# isolation.net
KiCad netlist of a schematic drawn in EAGLE
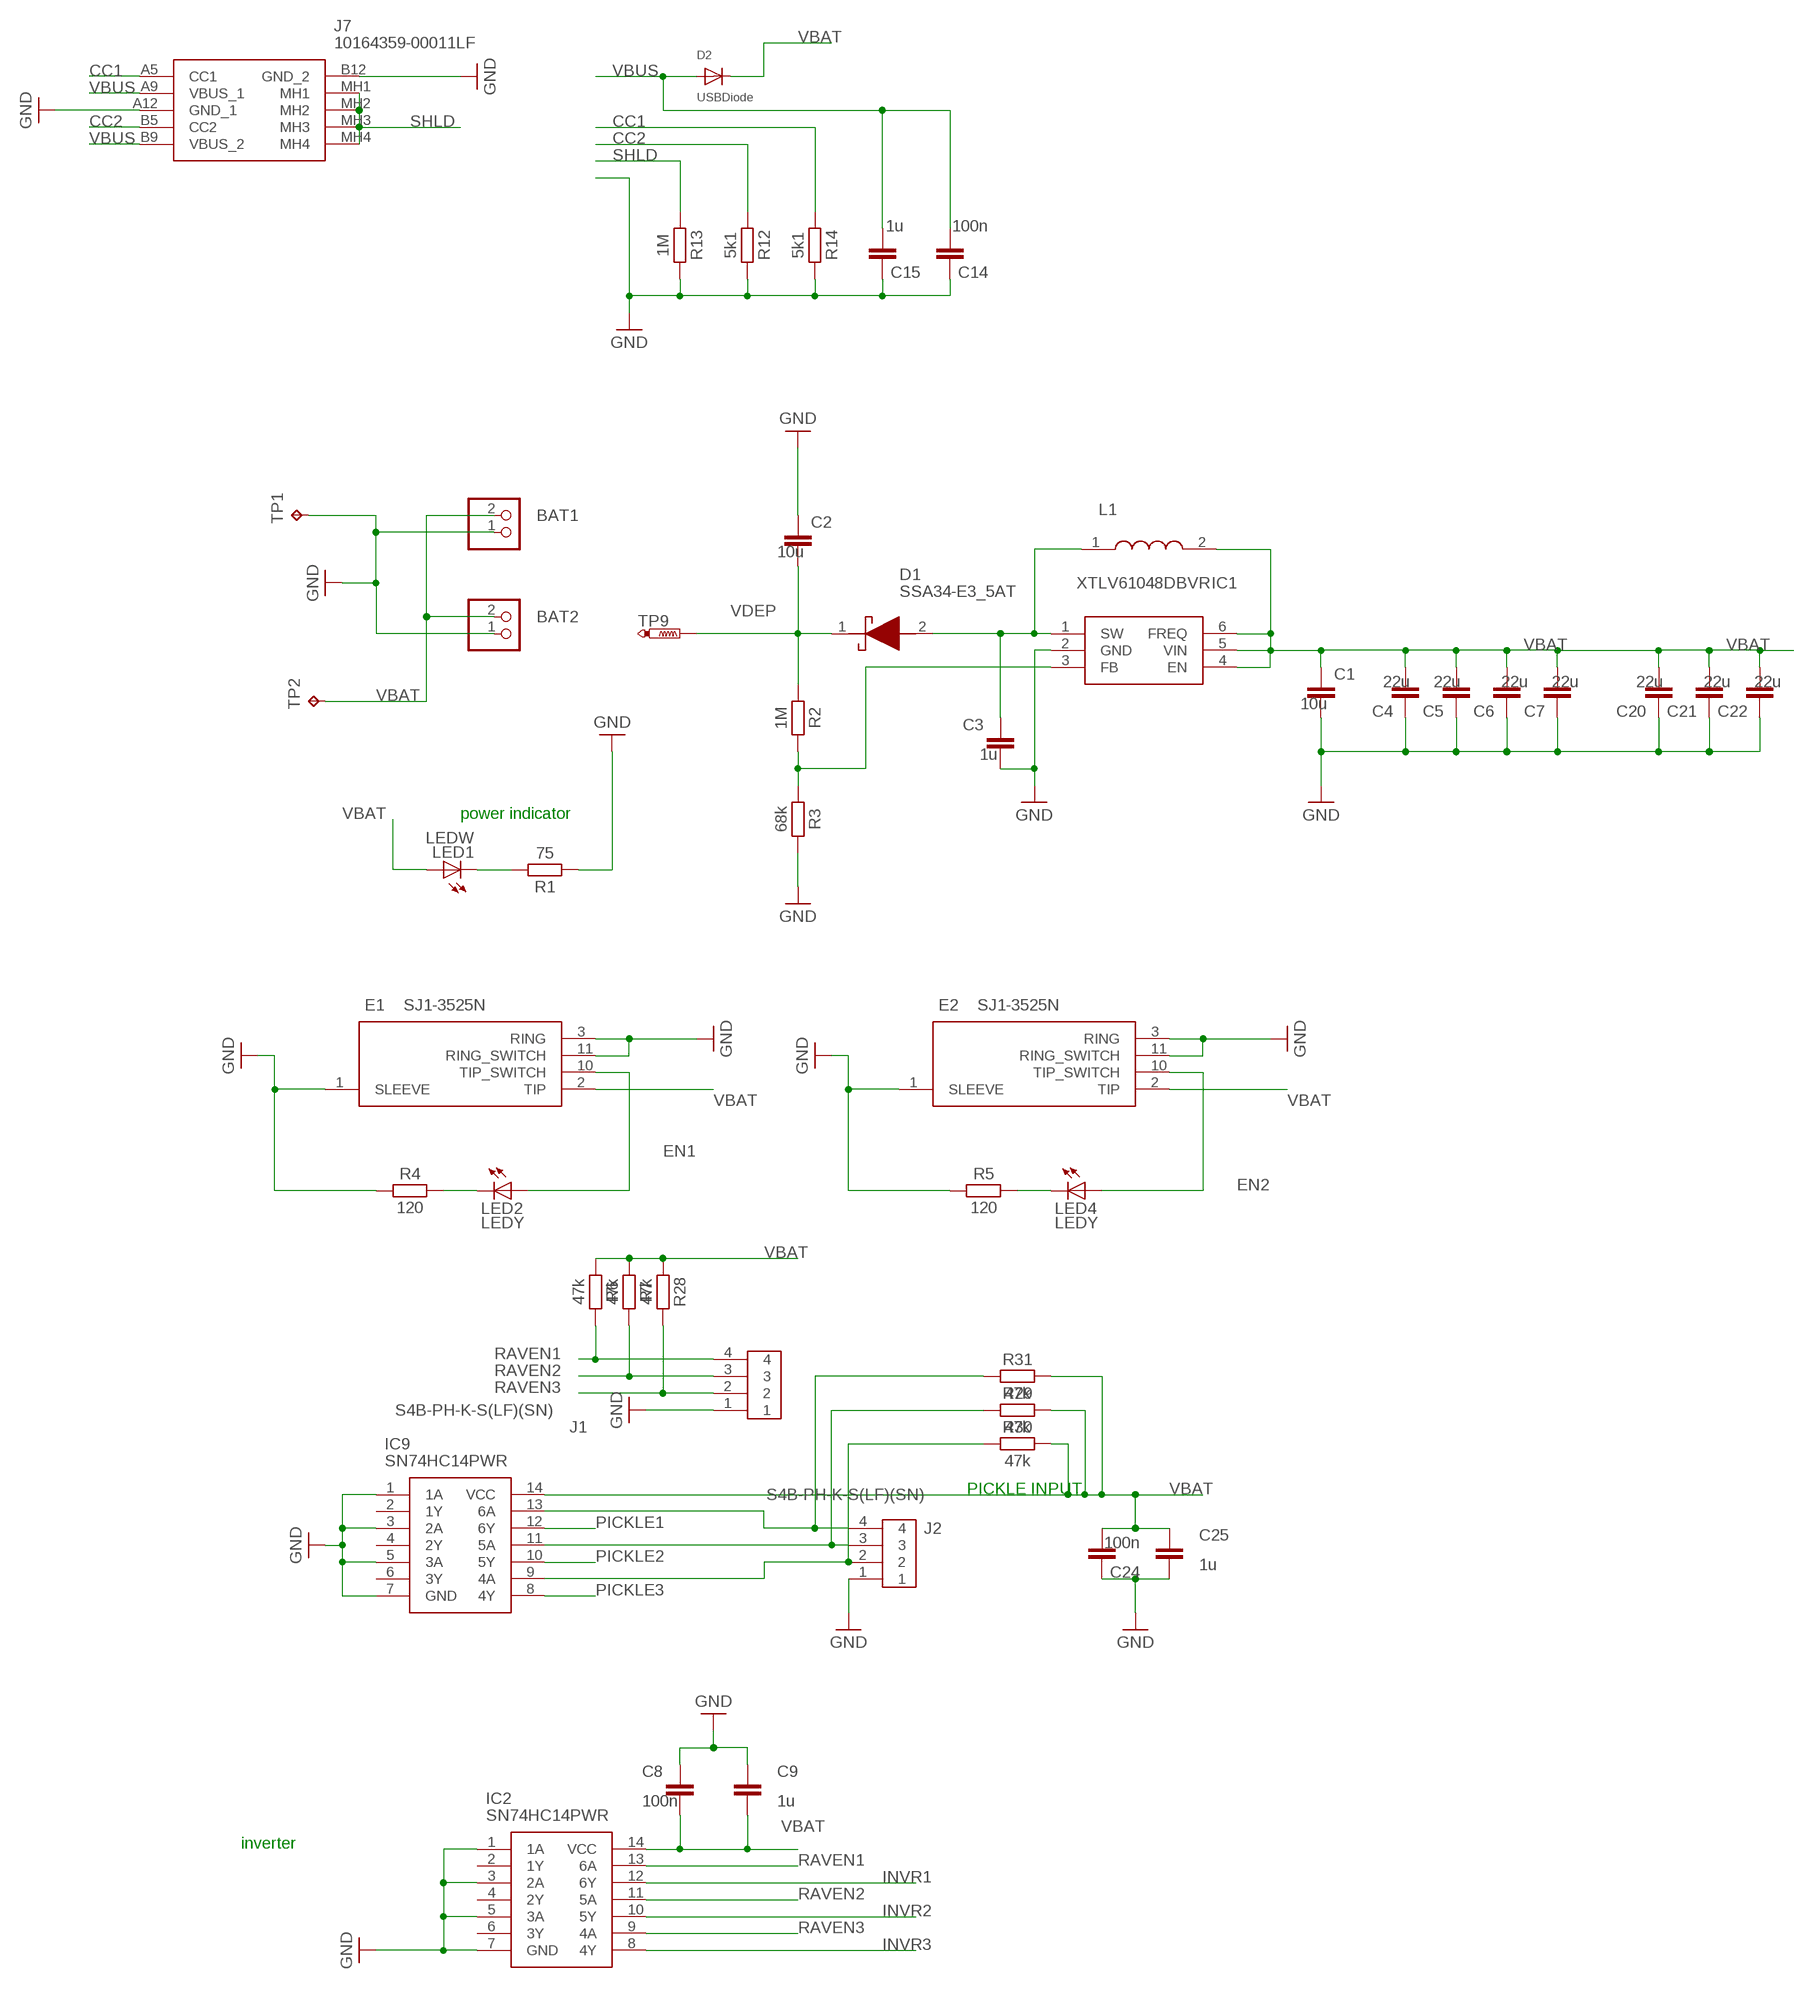
[diagram p0: schematic, sheet 1, part 1 of 2]
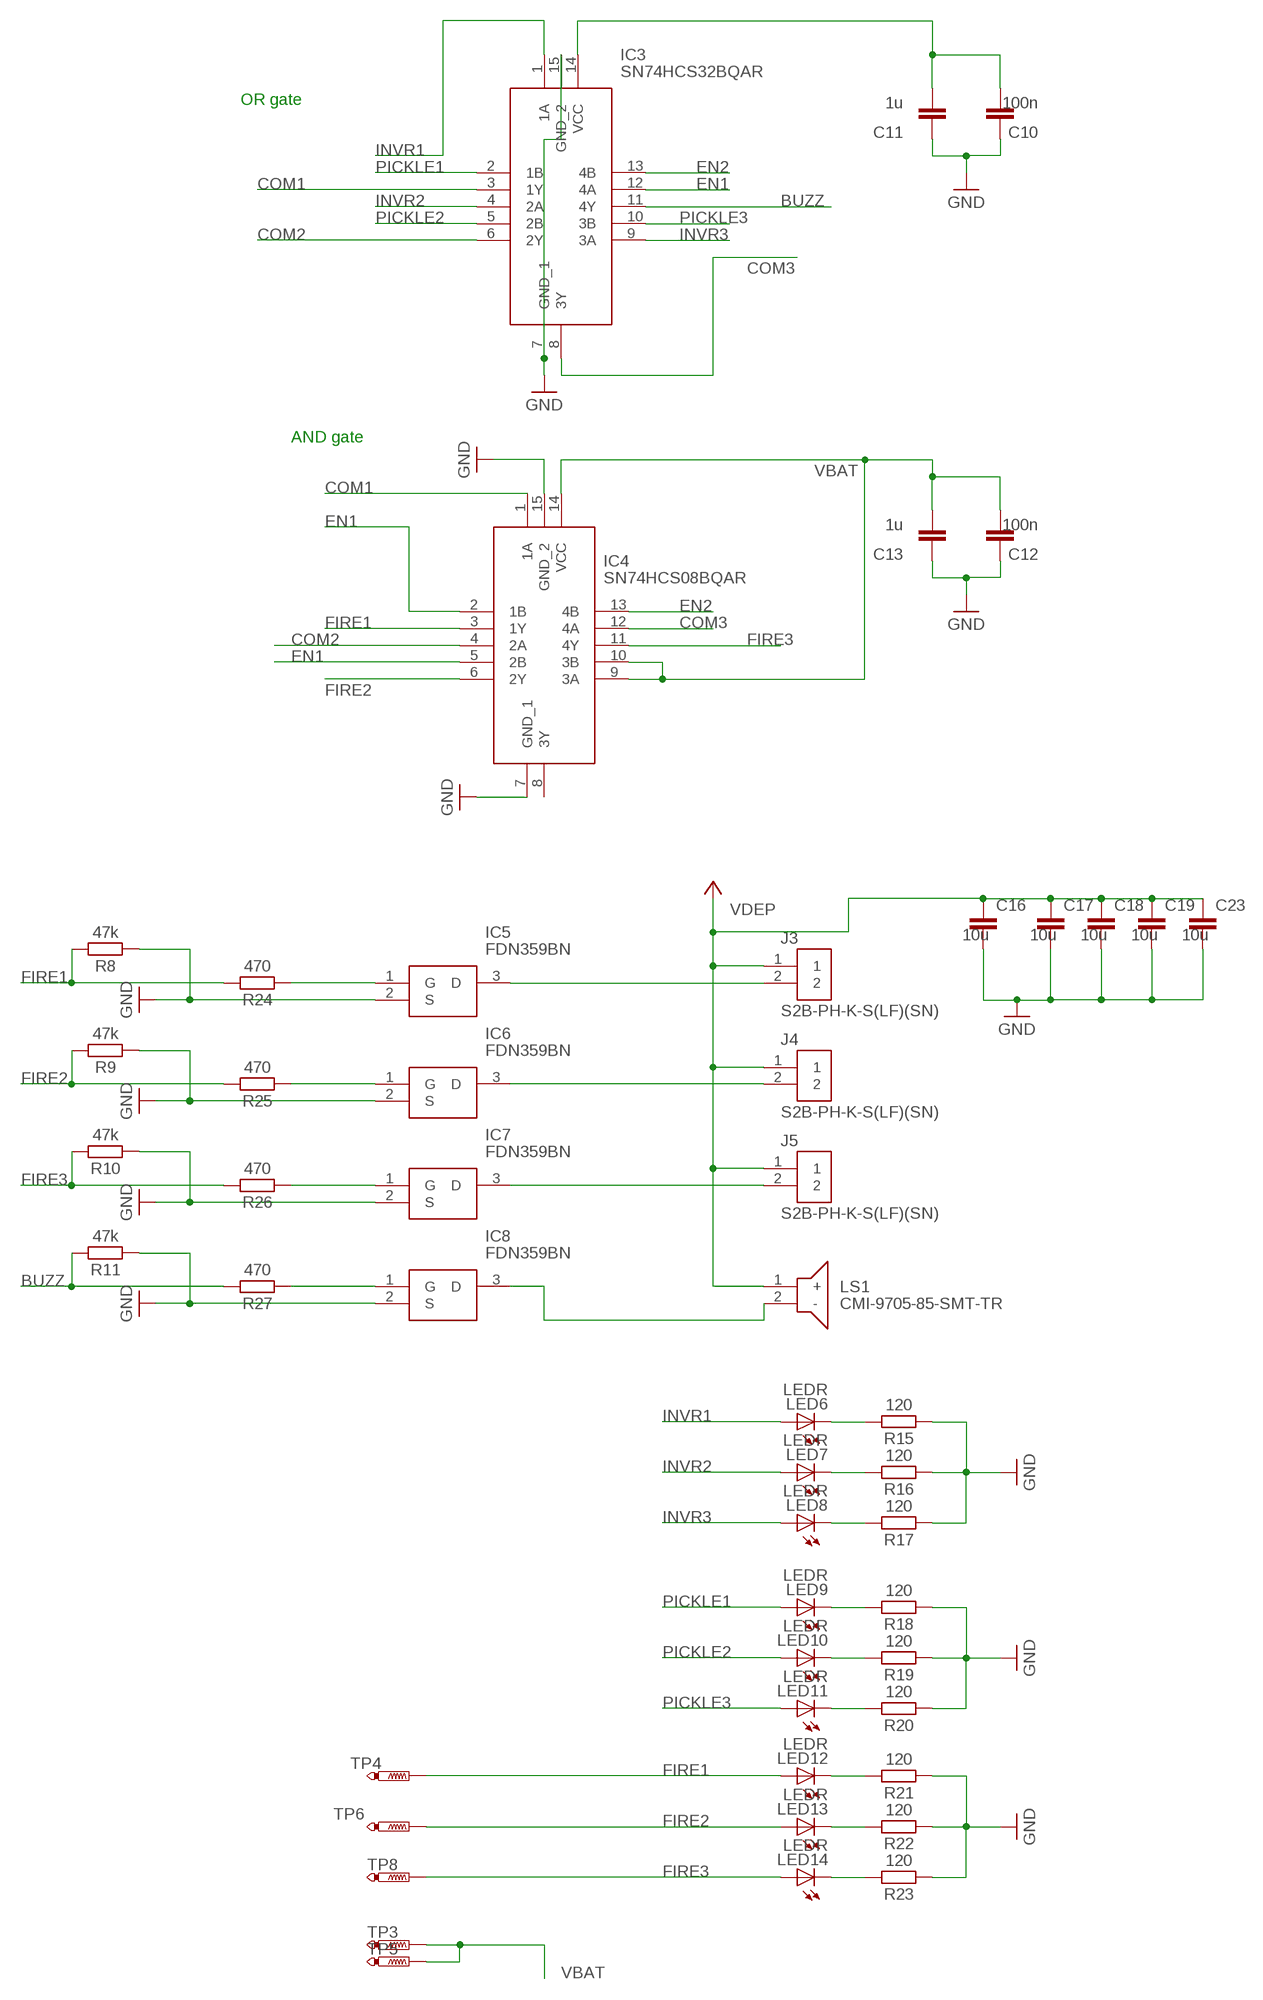
[diagram p1: schematic, sheet 1, part 2 of 2]

(export (version "E")
  (design (tool "Eeschema 10.0.6"))
  (components
    (comp (ref "BAT1")
      (value "JST_2PIN-THM-RA")
      (footprint "eagle-import:JST-PH-2-THM-RA")
      (libsource (lib "eagle-import") (part "JST_2PIN-THM-RA"))
    )
    (comp (ref "BAT2")
      (value "JST_2PIN-THM-RA")
      (footprint "eagle-import:JST-PH-2-THM-RA")
      (libsource (lib "eagle-import") (part "JST_2PIN-THM-RA"))
    )
    (comp (ref "C1")
      (value "10u")
      (footprint "eagle-import:CAPC1005X60")
      (libsource (lib "eagle-import") (part "CCHIP-0402(1005-METRIC)_"))
    )
    (comp (ref "C2")
      (value "10u")
      (footprint "eagle-import:CAPC1608X85")
      (libsource (lib "eagle-import") (part "CCHIP-0603(1608-METRIC)_"))
    )
    (comp (ref "C3")
      (value "1u")
      (footprint "eagle-import:CAPC1005X60")
      (libsource (lib "eagle-import") (part "CCHIP-0402(1005-METRIC)_"))
    )
    (comp (ref "C4")
      (value "22u")
      (footprint "eagle-import:CAPC1608X85")
      (libsource (lib "eagle-import") (part "CCHIP-0603(1608-METRIC)_"))
    )
    (comp (ref "C5")
      (value "22u")
      (footprint "eagle-import:CAPC1608X85")
      (libsource (lib "eagle-import") (part "CCHIP-0603(1608-METRIC)_"))
    )
    (comp (ref "C6")
      (value "22u")
      (footprint "eagle-import:CAPC1608X85")
      (libsource (lib "eagle-import") (part "CCHIP-0603(1608-METRIC)_"))
    )
    (comp (ref "C7")
      (value "22u")
      (footprint "eagle-import:CAPC1608X85")
      (libsource (lib "eagle-import") (part "CCHIP-0603(1608-METRIC)_"))
    )
    (comp (ref "C8")
      (value "100n")
      (footprint "eagle-import:CAPC1005X60")
      (libsource (lib "eagle-import") (part "CCHIP-0402(1005-METRIC)_"))
    )
    (comp (ref "C9")
      (value "1u")
      (footprint "eagle-import:CAPC1005X60")
      (libsource (lib "eagle-import") (part "CCHIP-0402(1005-METRIC)_"))
    )
    (comp (ref "C10")
      (value "100n")
      (footprint "eagle-import:CAPC1005X60")
      (libsource (lib "eagle-import") (part "CCHIP-0402(1005-METRIC)_"))
    )
    (comp (ref "C11")
      (value "1u")
      (footprint "eagle-import:CAPC1005X60")
      (libsource (lib "eagle-import") (part "CCHIP-0402(1005-METRIC)_"))
    )
    (comp (ref "C12")
      (value "100n")
      (footprint "eagle-import:CAPC1005X60")
      (libsource (lib "eagle-import") (part "CCHIP-0402(1005-METRIC)_"))
    )
    (comp (ref "C13")
      (value "1u")
      (footprint "eagle-import:CAPC1005X60")
      (libsource (lib "eagle-import") (part "CCHIP-0402(1005-METRIC)_"))
    )
    (comp (ref "C14")
      (value "100n")
      (footprint "eagle-import:CAPC1005X60")
      (libsource (lib "eagle-import") (part "CCHIP-0402(1005-METRIC)_"))
    )
    (comp (ref "C15")
      (value "1u")
      (footprint "eagle-import:CAPC1005X60")
      (libsource (lib "eagle-import") (part "CCHIP-0402(1005-METRIC)_"))
    )
    (comp (ref "C16")
      (value "10u")
      (footprint "eagle-import:CAPC1608X85")
      (libsource (lib "eagle-import") (part "CCHIP-0603(1608-METRIC)_"))
    )
    (comp (ref "C17")
      (value "10u")
      (footprint "eagle-import:CAPC1608X85")
      (libsource (lib "eagle-import") (part "CCHIP-0603(1608-METRIC)_"))
    )
    (comp (ref "C18")
      (value "10u")
      (footprint "eagle-import:CAPC1608X85")
      (libsource (lib "eagle-import") (part "CCHIP-0603(1608-METRIC)_"))
    )
    (comp (ref "C19")
      (value "10u")
      (footprint "eagle-import:CAPC1608X85")
      (libsource (lib "eagle-import") (part "CCHIP-0603(1608-METRIC)_"))
    )
    (comp (ref "C20")
      (value "22u")
      (footprint "eagle-import:CAPC1608X85")
      (libsource (lib "eagle-import") (part "CCHIP-0603(1608-METRIC)_"))
    )
    (comp (ref "C21")
      (value "22u")
      (footprint "eagle-import:CAPC1608X85")
      (libsource (lib "eagle-import") (part "CCHIP-0603(1608-METRIC)_"))
    )
    (comp (ref "C22")
      (value "22u")
      (footprint "eagle-import:CAPC1608X85")
      (libsource (lib "eagle-import") (part "CCHIP-0603(1608-METRIC)_"))
    )
    (comp (ref "C23")
      (value "10u")
      (footprint "eagle-import:CAPC1608X85")
      (libsource (lib "eagle-import") (part "CCHIP-0603(1608-METRIC)_"))
    )
    (comp (ref "C24")
      (value "100n")
      (footprint "eagle-import:CAPC1005X60")
      (libsource (lib "eagle-import") (part "CCHIP-0402(1005-METRIC)_"))
    )
    (comp (ref "C25")
      (value "1u")
      (footprint "eagle-import:CAPC1005X60")
      (libsource (lib "eagle-import") (part "CCHIP-0402(1005-METRIC)_"))
    )
    (comp (ref "D1")
      (value "SSA34-E3_5AT")
      (footprint "eagle-import:DIOM5127X229N")
      (fields
        (field (name "ARROW_PART_NUMBER") "SSA34-E3/5AT")
        (field (name "MOUSER_PART_NUMBER") "625-SSA34-E3/5AT")
      )
      (libsource (lib "eagle-import") (part "SSA34-E3_5AT"))
    )
    (comp (ref "D2")
      (value "USBDiode")
      (footprint "eagle-import:SOD-123FL")
      (libsource (lib "eagle-import") (part "DIODE_SOD-123FL"))
    )
    (comp (ref "E1")
      (value "SJ1-3525N")
      (footprint "eagle-import:SJ13525N")
      (libsource (lib "eagle-import") (part "SJ1-3525N"))
    )
    (comp (ref "E2")
      (value "SJ1-3525N")
      (footprint "eagle-import:SJ13525N")
      (libsource (lib "eagle-import") (part "SJ1-3525N"))
    )
    (comp (ref "IC1")
      (value "XTLV61048DBVR")
      (footprint "eagle-import:SOT95P280X145-6N")
      (libsource (lib "eagle-import") (part "XTLV61048DBVR"))
    )
    (comp (ref "IC2")
      (value "SN74HC14PWR")
      (footprint "eagle-import:SOP65P640X120-14N")
      (fields (field (name "MOUSER_PART_NUMBER") "595-SN74HC14PWR"))
      (libsource (lib "eagle-import") (part "SN74HC14PWR"))
    )
    (comp (ref "IC3")
      (value "SN74HCS32BQAR")
      (footprint "eagle-import:SN74HCS32BQAR")
      (fields (field (name "MOUSER_PART_NUMBER") "595-SN74HCS32BQAR"))
      (libsource (lib "eagle-import") (part "SN74HCS32BQAR"))
    )
    (comp (ref "IC4")
      (value "SN74HCS08BQAR")
      (footprint "eagle-import:SN74HCS08BQAR")
      (fields (field (name "MOUSER_PART_NUMBER") "595-SN74HCS08BQAR"))
      (libsource (lib "eagle-import") (part "SN74HCS08BQAR"))
    )
    (comp (ref "IC5")
      (value "FDN359BN")
      (footprint "eagle-import:SOT95P251X112-3N")
      (fields (field (name "MOUSER_PART_NUMBER") "512-FDN359BN"))
      (libsource (lib "eagle-import") (part "FDN359BN"))
    )
    (comp (ref "IC6")
      (value "FDN359BN")
      (footprint "eagle-import:SOT95P251X112-3N")
      (fields (field (name "MOUSER_PART_NUMBER") "512-FDN359BN"))
      (libsource (lib "eagle-import") (part "FDN359BN"))
    )
    (comp (ref "IC7")
      (value "FDN359BN")
      (footprint "eagle-import:SOT95P251X112-3N")
      (fields (field (name "MOUSER_PART_NUMBER") "512-FDN359BN"))
      (libsource (lib "eagle-import") (part "FDN359BN"))
    )
    (comp (ref "IC8")
      (value "FDN359BN")
      (footprint "eagle-import:SOT95P251X112-3N")
      (fields (field (name "MOUSER_PART_NUMBER") "512-FDN359BN"))
      (libsource (lib "eagle-import") (part "FDN359BN"))
    )
    (comp (ref "IC9")
      (value "SN74HC14PWR")
      (footprint "eagle-import:SOP65P640X120-14N")
      (fields (field (name "MOUSER_PART_NUMBER") "595-SN74HC14PWR"))
      (libsource (lib "eagle-import") (part "SN74HC14PWR"))
    )
    (comp (ref "J1")
      (value "S4B-PH-K-S(LF)(SN)")
      (footprint "eagle-import:S4B-PH-K-S(LF)(SN)")
      (fields
        (field (name "DIGIKEY_PARTNO") "455-1721-ND")
        (field (name "MANUFACTURER") "JST Sales America Inc.")
        (field (name "CREATED_BY") "PCBLayout.com")
      )
      (libsource (lib "eagle-import") (part "S4B-PH-K-S(LF)(SN)"))
    )
    (comp (ref "J2")
      (value "S4B-PH-K-S(LF)(SN)")
      (footprint "eagle-import:S4B-PH-K-S(LF)(SN)")
      (fields
        (field (name "DIGIKEY_PARTNO") "455-1721-ND")
        (field (name "MANUFACTURER") "JST Sales America Inc.")
        (field (name "CREATED_BY") "PCBLayout.com")
      )
      (libsource (lib "eagle-import") (part "S4B-PH-K-S(LF)(SN)"))
    )
    (comp (ref "J3")
      (value "S2B-PH-K-S(LF)(SN)")
      (footprint "eagle-import:S2B-PH-K-S(LF)(SN)")
      (fields
        (field (name "DIGI_KEY_PART_NUMBER") "455-1719-ND")
        (field (name "MANUFACTURER") "JST Sales America Inc.")
        (field (name "CREATED_BY") "PCBLayout.com")
      )
      (libsource (lib "eagle-import") (part "S2B-PH-K-S(LF)(SN)"))
    )
    (comp (ref "J4")
      (value "S2B-PH-K-S(LF)(SN)")
      (footprint "eagle-import:S2B-PH-K-S(LF)(SN)")
      (fields
        (field (name "DIGI_KEY_PART_NUMBER") "455-1719-ND")
        (field (name "MANUFACTURER") "JST Sales America Inc.")
        (field (name "CREATED_BY") "PCBLayout.com")
      )
      (libsource (lib "eagle-import") (part "S2B-PH-K-S(LF)(SN)"))
    )
    (comp (ref "J5")
      (value "S2B-PH-K-S(LF)(SN)")
      (footprint "eagle-import:S2B-PH-K-S(LF)(SN)")
      (fields
        (field (name "DIGI_KEY_PART_NUMBER") "455-1719-ND")
        (field (name "MANUFACTURER") "JST Sales America Inc.")
        (field (name "CREATED_BY") "PCBLayout.com")
      )
      (libsource (lib "eagle-import") (part "S2B-PH-K-S(LF)(SN)"))
    )
    (comp (ref "J7")
      (value "10164359-00011LF")
      (footprint "eagle-import:1016435900011LF")
      (fields (field (name "MOUSER_PART_NUMBER") "649-10164359-00011LF"))
      (libsource (lib "eagle-import") (part "10164359-00011LF"))
    )
    (comp (ref "L1")
      (value "10μH")
      (footprint "eagle-import:BMRF00060630100MA1")
      (fields (field (name "MANUFACTURER_PART_NUMBER") "BMRF00060630100MA1"))
      (libsource (lib "eagle-import") (part "BMRF00060630100MA1"))
    )
    (comp (ref "LED1")
      (value "LEDW")
      (footprint "eagle-import:CHIPLED_0805")
      (libsource (lib "eagle-import") (part "LEDCHIPLED_0805"))
    )
    (comp (ref "LED2")
      (value "LEDY")
      (footprint "eagle-import:CHIPLED_0805")
      (libsource (lib "eagle-import") (part "LEDCHIPLED_0805"))
    )
    (comp (ref "LED4")
      (value "LEDY")
      (footprint "eagle-import:CHIPLED_0805")
      (libsource (lib "eagle-import") (part "LEDCHIPLED_0805"))
    )
    (comp (ref "LED6")
      (value "LEDR")
      (footprint "eagle-import:CHIPLED_0805")
      (libsource (lib "eagle-import") (part "LEDCHIPLED_0805"))
    )
    (comp (ref "LED7")
      (value "LEDR")
      (footprint "eagle-import:CHIPLED_0805")
      (libsource (lib "eagle-import") (part "LEDCHIPLED_0805"))
    )
    (comp (ref "LED8")
      (value "LEDR")
      (footprint "eagle-import:CHIPLED_0805")
      (libsource (lib "eagle-import") (part "LEDCHIPLED_0805"))
    )
    (comp (ref "LED9")
      (value "LEDR")
      (footprint "eagle-import:CHIPLED_0805")
      (libsource (lib "eagle-import") (part "LEDCHIPLED_0805"))
    )
    (comp (ref "LED10")
      (value "LEDR")
      (footprint "eagle-import:CHIPLED_0805")
      (libsource (lib "eagle-import") (part "LEDCHIPLED_0805"))
    )
    (comp (ref "LED11")
      (value "LEDR")
      (footprint "eagle-import:CHIPLED_0805")
      (libsource (lib "eagle-import") (part "LEDCHIPLED_0805"))
    )
    (comp (ref "LED12")
      (value "LEDR")
      (footprint "eagle-import:CHIPLED_0805")
      (libsource (lib "eagle-import") (part "LEDCHIPLED_0805"))
    )
    (comp (ref "LED13")
      (value "LEDR")
      (footprint "eagle-import:CHIPLED_0805")
      (libsource (lib "eagle-import") (part "LEDCHIPLED_0805"))
    )
    (comp (ref "LED14")
      (value "LEDR")
      (footprint "eagle-import:CHIPLED_0805")
      (libsource (lib "eagle-import") (part "LEDCHIPLED_0805"))
    )
    (comp (ref "LS1")
      (value "CMI-9705-85-SMT-TR")
      (footprint "eagle-import:CMI970585SMTTR")
      (fields (field (name "MOUSER_PART_NUMBER") "490-CMI-9705-85SMTTR"))
      (libsource (lib "eagle-import") (part "CMI-9705-85-SMT-TR"))
    )
    (comp (ref "R1")
      (value "75")
      (footprint "eagle-import:RESC1608X60")
      (libsource (lib "eagle-import") (part "RCHIP-0603(1608-METRIC)_"))
    )
    (comp (ref "R2")
      (value "1M")
      (footprint "eagle-import:RESC1005X40")
      (libsource (lib "eagle-import") (part "RCHIP-0402(1005-METRIC)_"))
    )
    (comp (ref "R3")
      (value "68k")
      (footprint "eagle-import:RESC1608X60")
      (libsource (lib "eagle-import") (part "RCHIP-0603(1608-METRIC)_"))
    )
    (comp (ref "R4")
      (value "120")
      (footprint "eagle-import:RESC1005X40")
      (libsource (lib "eagle-import") (part "RCHIP-0402(1005-METRIC)_"))
    )
    (comp (ref "R5")
      (value "120")
      (footprint "eagle-import:RESC1005X40")
      (libsource (lib "eagle-import") (part "RCHIP-0402(1005-METRIC)_"))
    )
    (comp (ref "R6")
      (value "47k")
      (footprint "eagle-import:RESC1005X40")
      (libsource (lib "eagle-import") (part "RCHIP-0402(1005-METRIC)_"))
    )
    (comp (ref "R7")
      (value "47k")
      (footprint "eagle-import:RESC1005X40")
      (libsource (lib "eagle-import") (part "RCHIP-0402(1005-METRIC)_"))
    )
    (comp (ref "R8")
      (value "47k")
      (footprint "eagle-import:RESC1005X40")
      (libsource (lib "eagle-import") (part "RCHIP-0402(1005-METRIC)_"))
    )
    (comp (ref "R9")
      (value "47k")
      (footprint "eagle-import:RESC1005X40")
      (libsource (lib "eagle-import") (part "RCHIP-0402(1005-METRIC)_"))
    )
    (comp (ref "R10")
      (value "47k")
      (footprint "eagle-import:RESC1005X40")
      (libsource (lib "eagle-import") (part "RCHIP-0402(1005-METRIC)_"))
    )
    (comp (ref "R11")
      (value "47k")
      (footprint "eagle-import:RESC1005X40")
      (libsource (lib "eagle-import") (part "RCHIP-0402(1005-METRIC)_"))
    )
    (comp (ref "R12")
      (value "5k1")
      (footprint "eagle-import:RESC1005X40")
      (libsource (lib "eagle-import") (part "RCHIP-0402(1005-METRIC)_"))
    )
    (comp (ref "R13")
      (value "1M")
      (footprint "eagle-import:RESC1005X40")
      (libsource (lib "eagle-import") (part "RCHIP-0402(1005-METRIC)_"))
    )
    (comp (ref "R14")
      (value "5k1")
      (footprint "eagle-import:RESC1005X40")
      (libsource (lib "eagle-import") (part "RCHIP-0402(1005-METRIC)_"))
    )
    (comp (ref "R15")
      (value "120")
      (footprint "eagle-import:RESC1005X40")
      (libsource (lib "eagle-import") (part "RCHIP-0402(1005-METRIC)_"))
    )
    (comp (ref "R16")
      (value "120")
      (footprint "eagle-import:RESC1005X40")
      (libsource (lib "eagle-import") (part "RCHIP-0402(1005-METRIC)_"))
    )
    (comp (ref "R17")
      (value "120")
      (footprint "eagle-import:RESC1005X40")
      (libsource (lib "eagle-import") (part "RCHIP-0402(1005-METRIC)_"))
    )
    (comp (ref "R18")
      (value "120")
      (footprint "eagle-import:RESC1005X40")
      (libsource (lib "eagle-import") (part "RCHIP-0402(1005-METRIC)_"))
    )
    (comp (ref "R19")
      (value "120")
      (footprint "eagle-import:RESC1005X40")
      (libsource (lib "eagle-import") (part "RCHIP-0402(1005-METRIC)_"))
    )
    (comp (ref "R20")
      (value "120")
      (footprint "eagle-import:RESC1005X40")
      (libsource (lib "eagle-import") (part "RCHIP-0402(1005-METRIC)_"))
    )
    (comp (ref "R21")
      (value "120")
      (footprint "eagle-import:RESC1005X40")
      (libsource (lib "eagle-import") (part "RCHIP-0402(1005-METRIC)_"))
    )
    (comp (ref "R22")
      (value "120")
      (footprint "eagle-import:RESC1005X40")
      (libsource (lib "eagle-import") (part "RCHIP-0402(1005-METRIC)_"))
    )
    (comp (ref "R23")
      (value "120")
      (footprint "eagle-import:RESC1005X40")
      (libsource (lib "eagle-import") (part "RCHIP-0402(1005-METRIC)_"))
    )
    (comp (ref "R24")
      (value "470")
      (footprint "eagle-import:RESC1005X40")
      (libsource (lib "eagle-import") (part "RCHIP-0402(1005-METRIC)_"))
    )
    (comp (ref "R25")
      (value "470")
      (footprint "eagle-import:RESC1005X40")
      (libsource (lib "eagle-import") (part "RCHIP-0402(1005-METRIC)_"))
    )
    (comp (ref "R26")
      (value "470")
      (footprint "eagle-import:RESC1005X40")
      (libsource (lib "eagle-import") (part "RCHIP-0402(1005-METRIC)_"))
    )
    (comp (ref "R27")
      (value "470")
      (footprint "eagle-import:RESC1005X40")
      (libsource (lib "eagle-import") (part "RCHIP-0402(1005-METRIC)_"))
    )
    (comp (ref "R28")
      (value "47k")
      (footprint "eagle-import:RESC1005X40")
      (libsource (lib "eagle-import") (part "RCHIP-0402(1005-METRIC)_"))
    )
    (comp (ref "R29")
      (value "47k")
      (footprint "eagle-import:RESC1005X40")
      (libsource (lib "eagle-import") (part "RCHIP-0402(1005-METRIC)_"))
    )
    (comp (ref "R30")
      (value "47k")
      (footprint "eagle-import:RESC1005X40")
      (libsource (lib "eagle-import") (part "RCHIP-0402(1005-METRIC)_"))
    )
    (comp (ref "R31")
      (value "47k")
      (footprint "eagle-import:RESC1005X40")
      (libsource (lib "eagle-import") (part "RCHIP-0402(1005-METRIC)_"))
    )
    (comp (ref "TP1")
      (value "TPPAD1-13")
      (footprint "eagle-import:P1-13")
      (libsource (lib "eagle-import") (part "TPPAD1-13"))
    )
    (comp (ref "TP2")
      (value "TPPAD1-17")
      (footprint "eagle-import:P1-17")
      (libsource (lib "eagle-import") (part "TPPAD1-17"))
    )
    (comp (ref "TP3")
      (value "PTR1PAD1-13")
      (footprint "eagle-import:P1-13")
      (libsource (lib "eagle-import") (part "PTR1PAD1-13"))
    )
    (comp (ref "TP4")
      (value "PTR1PAD1-13")
      (footprint "eagle-import:P1-13")
      (libsource (lib "eagle-import") (part "PTR1PAD1-13"))
    )
    (comp (ref "TP5")
      (value "PTR1PAD1-13")
      (footprint "eagle-import:P1-13")
      (libsource (lib "eagle-import") (part "PTR1PAD1-13"))
    )
    (comp (ref "TP6")
      (value "PTR1PAD1-13")
      (footprint "eagle-import:P1-13")
      (libsource (lib "eagle-import") (part "PTR1PAD1-13"))
    )
    (comp (ref "TP8")
      (value "PTR1PAD1-13")
      (footprint "eagle-import:P1-13")
      (libsource (lib "eagle-import") (part "PTR1PAD1-13"))
    )
    (comp (ref "TP9")
      (value "PTR1PAD1-13")
      (footprint "eagle-import:P1-13")
      (libsource (lib "eagle-import") (part "PTR1PAD1-13"))
    )
  )
  (nets
    (net (code "1") (name "/BUZZ") (class "Default")
      (node (ref "IC3") (pin "11") (pinfunction "4Y_11") (pintype "bidirectional"))
      (node (ref "R11") (pin "2") (pinfunction "2_2") (pintype "passive"))
      (node (ref "R27") (pin "2") (pinfunction "2_2") (pintype "passive"))
    )
    (net (code "2") (name "/CC1") (class "Default")
      (node (ref "J7") (pin "A5") (pinfunction "CC1_A5") (pintype "bidirectional"))
      (node (ref "R14") (pin "1") (pinfunction "1_1") (pintype "passive"))
    )
    (net (code "3") (name "/CC2") (class "Default")
      (node (ref "J7") (pin "B5") (pinfunction "CC2_B5") (pintype "bidirectional"))
      (node (ref "R12") (pin "1") (pinfunction "1_1") (pintype "passive"))
    )
    (net (code "4") (name "/COM1") (class "Default")
      (node (ref "IC3") (pin "3") (pinfunction "1Y_3") (pintype "bidirectional"))
      (node (ref "IC4") (pin "1") (pinfunction "1A_1") (pintype "bidirectional"))
    )
    (net (code "5") (name "/COM2") (class "Default")
      (node (ref "IC3") (pin "6") (pinfunction "2Y_6") (pintype "bidirectional"))
      (node (ref "IC4") (pin "4") (pinfunction "2A_4") (pintype "bidirectional"))
    )
    (net (code "6") (name "/COM3") (class "Default")
      (node (ref "IC3") (pin "8") (pinfunction "3Y_8") (pintype "bidirectional"))
      (node (ref "IC4") (pin "12") (pinfunction "4A_12") (pintype "bidirectional"))
    )
    (net (code "7") (name "/EN1") (class "Default")
      (node (ref "E1") (pin "10") (pinfunction "TIP_SWITCH_10") (pintype "bidirectional"))
      (node (ref "IC3") (pin "12") (pinfunction "4A_12") (pintype "bidirectional"))
      (node (ref "IC4") (pin "2") (pinfunction "1B_2") (pintype "bidirectional"))
      (node (ref "IC4") (pin "5") (pinfunction "2B_5") (pintype "bidirectional"))
      (node (ref "LED2") (pin "A") (pinfunction "A_A") (pintype "passive"))
    )
    (net (code "8") (name "/EN2") (class "Default")
      (node (ref "E2") (pin "10") (pinfunction "TIP_SWITCH_10") (pintype "bidirectional"))
      (node (ref "IC3") (pin "13") (pinfunction "4B_13") (pintype "bidirectional"))
      (node (ref "IC4") (pin "13") (pinfunction "4B_13") (pintype "bidirectional"))
      (node (ref "LED4") (pin "A") (pinfunction "A_A") (pintype "passive"))
    )
    (net (code "9") (name "/FIRE1") (class "Default")
      (node (ref "IC4") (pin "3") (pinfunction "1Y_3") (pintype "bidirectional"))
      (node (ref "LED12") (pin "A") (pinfunction "A_A") (pintype "passive"))
      (node (ref "R24") (pin "2") (pinfunction "2_2") (pintype "passive"))
      (node (ref "R8") (pin "2") (pinfunction "2_2") (pintype "passive"))
      (node (ref "TP4") (pin "TP") (pinfunction "TP_TP") (pintype "input"))
    )
    (net (code "10") (name "/FIRE2") (class "Default")
      (node (ref "IC4") (pin "6") (pinfunction "2Y_6") (pintype "bidirectional"))
      (node (ref "LED13") (pin "A") (pinfunction "A_A") (pintype "passive"))
      (node (ref "R25") (pin "2") (pinfunction "2_2") (pintype "passive"))
      (node (ref "R9") (pin "2") (pinfunction "2_2") (pintype "passive"))
      (node (ref "TP6") (pin "TP") (pinfunction "TP_TP") (pintype "input"))
    )
    (net (code "11") (name "/FIRE3") (class "Default")
      (node (ref "IC4") (pin "11") (pinfunction "4Y_11") (pintype "bidirectional"))
      (node (ref "LED14") (pin "A") (pinfunction "A_A") (pintype "passive"))
      (node (ref "R10") (pin "2") (pinfunction "2_2") (pintype "passive"))
      (node (ref "R26") (pin "2") (pinfunction "2_2") (pintype "passive"))
      (node (ref "TP8") (pin "TP") (pinfunction "TP_TP") (pintype "input"))
    )
    (net (code "12") (name "/INVR1") (class "Default")
      (node (ref "IC2") (pin "12") (pinfunction "6Y_12") (pintype "bidirectional"))
      (node (ref "IC3") (pin "1") (pinfunction "1A_1") (pintype "bidirectional"))
      (node (ref "LED6") (pin "A") (pinfunction "A_A") (pintype "passive"))
    )
    (net (code "13") (name "/INVR2") (class "Default")
      (node (ref "IC2") (pin "10") (pinfunction "5Y_10") (pintype "bidirectional"))
      (node (ref "IC3") (pin "4") (pinfunction "2A_4") (pintype "bidirectional"))
      (node (ref "LED7") (pin "A") (pinfunction "A_A") (pintype "passive"))
    )
    (net (code "14") (name "/INVR3") (class "Default")
      (node (ref "IC2") (pin "8") (pinfunction "4Y_8") (pintype "bidirectional"))
      (node (ref "IC3") (pin "9") (pinfunction "3A_9") (pintype "bidirectional"))
      (node (ref "LED8") (pin "A") (pinfunction "A_A") (pintype "passive"))
    )
    (net (code "15") (name "/PICKLE1") (class "Default")
      (node (ref "IC3") (pin "2") (pinfunction "1B_2") (pintype "bidirectional"))
      (node (ref "IC9") (pin "12") (pinfunction "6Y_12") (pintype "bidirectional"))
      (node (ref "LED9") (pin "A") (pinfunction "A_A") (pintype "passive"))
    )
    (net (code "16") (name "/PICKLE2") (class "Default")
      (node (ref "IC3") (pin "5") (pinfunction "2B_5") (pintype "bidirectional"))
      (node (ref "IC9") (pin "10") (pinfunction "5Y_10") (pintype "bidirectional"))
      (node (ref "LED10") (pin "A") (pinfunction "A_A") (pintype "passive"))
    )
    (net (code "17") (name "/PICKLE3") (class "Default")
      (node (ref "IC3") (pin "10") (pinfunction "3B_10") (pintype "bidirectional"))
      (node (ref "IC9") (pin "8") (pinfunction "4Y_8") (pintype "bidirectional"))
      (node (ref "LED11") (pin "A") (pinfunction "A_A") (pintype "passive"))
    )
    (net (code "18") (name "/RAVEN1") (class "Default")
      (node (ref "IC2") (pin "13") (pinfunction "6A_13") (pintype "bidirectional"))
      (node (ref "J1") (pin "4") (pinfunction "4_4") (pintype "passive"))
      (node (ref "R6") (pin "2") (pinfunction "2_2") (pintype "passive"))
    )
    (net (code "19") (name "/RAVEN2") (class "Default")
      (node (ref "IC2") (pin "11") (pinfunction "5A_11") (pintype "bidirectional"))
      (node (ref "J1") (pin "3") (pinfunction "3_3") (pintype "passive"))
      (node (ref "R7") (pin "2") (pinfunction "2_2") (pintype "passive"))
    )
    (net (code "20") (name "/RAVEN3") (class "Default")
      (node (ref "IC2") (pin "9") (pinfunction "4A_9") (pintype "bidirectional"))
      (node (ref "J1") (pin "2") (pinfunction "2_2") (pintype "passive"))
      (node (ref "R28") (pin "2") (pinfunction "2_2") (pintype "passive"))
    )
    (net (code "21") (name "/SHLD") (class "Default")
      (node (ref "J7") (pin "MH1") (pinfunction "MH1_MH1") (pintype "bidirectional"))
      (node (ref "J7") (pin "MH2") (pinfunction "MH2_MH2") (pintype "bidirectional"))
      (node (ref "J7") (pin "MH3") (pinfunction "MH3_MH3") (pintype "bidirectional"))
      (node (ref "J7") (pin "MH4") (pinfunction "MH4_MH4") (pintype "bidirectional"))
      (node (ref "R13") (pin "1") (pinfunction "1_1") (pintype "passive"))
    )
    (net (code "22") (name "/VBAT") (class "Default")
      (node (ref "BAT1") (pin "2") (pinfunction "1_2") (pintype "passive"))
      (node (ref "BAT2") (pin "2") (pinfunction "1_2") (pintype "passive"))
      (node (ref "C1") (pin "1") (pinfunction "1_1") (pintype "passive"))
      (node (ref "C10") (pin "2") (pinfunction "2_2") (pintype "passive"))
      (node (ref "C11") (pin "2") (pinfunction "2_2") (pintype "passive"))
      (node (ref "C12") (pin "2") (pinfunction "2_2") (pintype "passive"))
      (node (ref "C13") (pin "2") (pinfunction "2_2") (pintype "passive"))
      (node (ref "C20") (pin "2") (pinfunction "2_2") (pintype "passive"))
      (node (ref "C21") (pin "2") (pinfunction "2_2") (pintype "passive"))
      (node (ref "C22") (pin "2") (pinfunction "2_2") (pintype "passive"))
      (node (ref "C24") (pin "2") (pinfunction "2_2") (pintype "passive"))
      (node (ref "C25") (pin "1") (pinfunction "1_1") (pintype "passive"))
      (node (ref "C4") (pin "2") (pinfunction "2_2") (pintype "passive"))
      (node (ref "C5") (pin "2") (pinfunction "2_2") (pintype "passive"))
      (node (ref "C6") (pin "2") (pinfunction "2_2") (pintype "passive"))
      (node (ref "C7") (pin "2") (pinfunction "2_2") (pintype "passive"))
      (node (ref "C8") (pin "2") (pinfunction "2_2") (pintype "passive"))
      (node (ref "C9") (pin "2") (pinfunction "2_2") (pintype "passive"))
      (node (ref "D2") (pin "C") (pinfunction "C_C") (pintype "passive"))
      (node (ref "E1") (pin "2") (pinfunction "TIP_2") (pintype "bidirectional"))
      (node (ref "E2") (pin "2") (pinfunction "TIP_2") (pintype "bidirectional"))
      (node (ref "IC1") (pin "4") (pinfunction "EN_4") (pintype "bidirectional"))
      (node (ref "IC1") (pin "5") (pinfunction "VIN_5") (pintype "bidirectional"))
      (node (ref "IC1") (pin "6") (pinfunction "FREQ_6") (pintype "bidirectional"))
      (node (ref "IC2") (pin "14") (pinfunction "VCC_14") (pintype "bidirectional"))
      (node (ref "IC3") (pin "14") (pinfunction "VCC_14") (pintype "bidirectional"))
      (node (ref "IC4") (pin "10") (pinfunction "3B_10") (pintype "bidirectional"))
      (node (ref "IC4") (pin "14") (pinfunction "VCC_14") (pintype "bidirectional"))
      (node (ref "IC4") (pin "9") (pinfunction "3A_9") (pintype "bidirectional"))
      (node (ref "IC9") (pin "14") (pinfunction "VCC_14") (pintype "bidirectional"))
      (node (ref "L1") (pin "2") (pinfunction "2_2") (pintype "bidirectional"))
      (node (ref "LED1") (pin "A") (pinfunction "A_A") (pintype "passive"))
      (node (ref "R28") (pin "1") (pinfunction "1_1") (pintype "passive"))
      (node (ref "R29") (pin "2") (pinfunction "2_2") (pintype "passive"))
      (node (ref "R30") (pin "2") (pinfunction "2_2") (pintype "passive"))
      (node (ref "R31") (pin "2") (pinfunction "2_2") (pintype "passive"))
      (node (ref "R6") (pin "1") (pinfunction "1_1") (pintype "passive"))
      (node (ref "R7") (pin "1") (pinfunction "1_1") (pintype "passive"))
      (node (ref "TP2") (pin "TP") (pinfunction "TP_TP") (pintype "input"))
      (node (ref "TP3") (pin "TP") (pinfunction "TP_TP") (pintype "input"))
      (node (ref "TP5") (pin "TP") (pinfunction "TP_TP") (pintype "input"))
    )
    (net (code "23") (name "/VBUS") (class "Default")
      (node (ref "C14") (pin "2") (pinfunction "2_2") (pintype "passive"))
      (node (ref "C15") (pin "2") (pinfunction "2_2") (pintype "passive"))
      (node (ref "D2") (pin "A") (pinfunction "A_A") (pintype "passive"))
      (node (ref "J7") (pin "A9") (pinfunction "VBUS_1_A9") (pintype "bidirectional"))
      (node (ref "J7") (pin "B9") (pinfunction "VBUS_2_B9") (pintype "bidirectional"))
    )
    (net (code "24") (name "GND") (class "Default")
      (node (ref "BAT1") (pin "1") (pinfunction "2_1") (pintype "passive"))
      (node (ref "BAT2") (pin "1") (pinfunction "2_1") (pintype "passive"))
      (node (ref "C1") (pin "2") (pinfunction "2_2") (pintype "passive"))
      (node (ref "C10") (pin "1") (pinfunction "1_1") (pintype "passive"))
      (node (ref "C11") (pin "1") (pinfunction "1_1") (pintype "passive"))
      (node (ref "C12") (pin "1") (pinfunction "1_1") (pintype "passive"))
      (node (ref "C13") (pin "1") (pinfunction "1_1") (pintype "passive"))
      (node (ref "C14") (pin "1") (pinfunction "1_1") (pintype "passive"))
      (node (ref "C15") (pin "1") (pinfunction "1_1") (pintype "passive"))
      (node (ref "C16") (pin "2") (pinfunction "2_2") (pintype "passive"))
      (node (ref "C17") (pin "2") (pinfunction "2_2") (pintype "passive"))
      (node (ref "C18") (pin "2") (pinfunction "2_2") (pintype "passive"))
      (node (ref "C19") (pin "2") (pinfunction "2_2") (pintype "passive"))
      (node (ref "C2") (pin "1") (pinfunction "1_1") (pintype "passive"))
      (node (ref "C20") (pin "1") (pinfunction "1_1") (pintype "passive"))
      (node (ref "C21") (pin "1") (pinfunction "1_1") (pintype "passive"))
      (node (ref "C22") (pin "1") (pinfunction "1_1") (pintype "passive"))
      (node (ref "C23") (pin "2") (pinfunction "2_2") (pintype "passive"))
      (node (ref "C24") (pin "1") (pinfunction "1_1") (pintype "passive"))
      (node (ref "C25") (pin "2") (pinfunction "2_2") (pintype "passive"))
      (node (ref "C3") (pin "2") (pinfunction "2_2") (pintype "passive"))
      (node (ref "C4") (pin "1") (pinfunction "1_1") (pintype "passive"))
      (node (ref "C5") (pin "1") (pinfunction "1_1") (pintype "passive"))
      (node (ref "C6") (pin "1") (pinfunction "1_1") (pintype "passive"))
      (node (ref "C7") (pin "1") (pinfunction "1_1") (pintype "passive"))
      (node (ref "C8") (pin "1") (pinfunction "1_1") (pintype "passive"))
      (node (ref "C9") (pin "1") (pinfunction "1_1") (pintype "passive"))
      (node (ref "E1") (pin "1") (pinfunction "SLEEVE_1") (pintype "bidirectional"))
      (node (ref "E1") (pin "11") (pinfunction "RING_SWITCH_11") (pintype "bidirectional"))
      (node (ref "E1") (pin "3") (pinfunction "RING_3") (pintype "bidirectional"))
      (node (ref "E2") (pin "1") (pinfunction "SLEEVE_1") (pintype "bidirectional"))
      (node (ref "E2") (pin "11") (pinfunction "RING_SWITCH_11") (pintype "bidirectional"))
      (node (ref "E2") (pin "3") (pinfunction "RING_3") (pintype "bidirectional"))
      (node (ref "IC1") (pin "2") (pinfunction "GND_2") (pintype "bidirectional"))
      (node (ref "IC2") (pin "1") (pinfunction "1A_1") (pintype "bidirectional"))
      (node (ref "IC2") (pin "3") (pinfunction "2A_3") (pintype "bidirectional"))
      (node (ref "IC2") (pin "5") (pinfunction "3A_5") (pintype "bidirectional"))
      (node (ref "IC2") (pin "7") (pinfunction "GND_7") (pintype "bidirectional"))
      (node (ref "IC3") (pin "15") (pinfunction "GND_2_15") (pintype "bidirectional"))
      (node (ref "IC3") (pin "7") (pinfunction "GND_1_7") (pintype "bidirectional"))
      (node (ref "IC4") (pin "15") (pinfunction "GND_2_15") (pintype "bidirectional"))
      (node (ref "IC4") (pin "7") (pinfunction "GND_1_7") (pintype "bidirectional"))
      (node (ref "IC5") (pin "2") (pinfunction "S_2") (pintype "bidirectional"))
      (node (ref "IC6") (pin "2") (pinfunction "S_2") (pintype "bidirectional"))
      (node (ref "IC7") (pin "2") (pinfunction "S_2") (pintype "bidirectional"))
      (node (ref "IC8") (pin "2") (pinfunction "S_2") (pintype "bidirectional"))
      (node (ref "IC9") (pin "1") (pinfunction "1A_1") (pintype "bidirectional"))
      (node (ref "IC9") (pin "3") (pinfunction "2A_3") (pintype "bidirectional"))
      (node (ref "IC9") (pin "5") (pinfunction "3A_5") (pintype "bidirectional"))
      (node (ref "IC9") (pin "7") (pinfunction "GND_7") (pintype "bidirectional"))
      (node (ref "J1") (pin "1") (pinfunction "1_1") (pintype "passive"))
      (node (ref "J2") (pin "1") (pinfunction "1_1") (pintype "passive"))
      (node (ref "J7") (pin "A12") (pinfunction "GND_1_A12") (pintype "bidirectional"))
      (node (ref "J7") (pin "B12") (pinfunction "GND_2_B12") (pintype "bidirectional"))
      (node (ref "R1") (pin "1") (pinfunction "1_1") (pintype "passive"))
      (node (ref "R10") (pin "1") (pinfunction "1_1") (pintype "passive"))
      (node (ref "R11") (pin "1") (pinfunction "1_1") (pintype "passive"))
      (node (ref "R12") (pin "2") (pinfunction "2_2") (pintype "passive"))
      (node (ref "R13") (pin "2") (pinfunction "2_2") (pintype "passive"))
      (node (ref "R14") (pin "2") (pinfunction "2_2") (pintype "passive"))
      (node (ref "R15") (pin "1") (pinfunction "1_1") (pintype "passive"))
      (node (ref "R16") (pin "1") (pinfunction "1_1") (pintype "passive"))
      (node (ref "R17") (pin "1") (pinfunction "1_1") (pintype "passive"))
      (node (ref "R18") (pin "1") (pinfunction "1_1") (pintype "passive"))
      (node (ref "R19") (pin "1") (pinfunction "1_1") (pintype "passive"))
      (node (ref "R20") (pin "1") (pinfunction "1_1") (pintype "passive"))
      (node (ref "R21") (pin "1") (pinfunction "1_1") (pintype "passive"))
      (node (ref "R22") (pin "1") (pinfunction "1_1") (pintype "passive"))
      (node (ref "R23") (pin "1") (pinfunction "1_1") (pintype "passive"))
      (node (ref "R3") (pin "2") (pinfunction "2_2") (pintype "passive"))
      (node (ref "R4") (pin "1") (pinfunction "1_1") (pintype "passive"))
      (node (ref "R5") (pin "1") (pinfunction "1_1") (pintype "passive"))
      (node (ref "R8") (pin "1") (pinfunction "1_1") (pintype "passive"))
      (node (ref "R9") (pin "1") (pinfunction "1_1") (pintype "passive"))
      (node (ref "TP1") (pin "TP") (pinfunction "TP_TP") (pintype "input"))
    )
    (net (code "25") (name "Net-(D1-A)") (class "Default")
      (node (ref "C3") (pin "1") (pinfunction "1_1") (pintype "passive"))
      (node (ref "D1") (pin "2") (pinfunction "A_2") (pintype "bidirectional"))
      (node (ref "IC1") (pin "1") (pinfunction "SW_1") (pintype "bidirectional"))
      (node (ref "L1") (pin "1") (pinfunction "1_1") (pintype "bidirectional"))
    )
    (net (code "26") (name "Net-(IC1-FB)") (class "Default")
      (node (ref "IC1") (pin "3") (pinfunction "FB_3") (pintype "bidirectional"))
      (node (ref "R2") (pin "2") (pinfunction "2_2") (pintype "passive"))
      (node (ref "R3") (pin "1") (pinfunction "1_1") (pintype "passive"))
    )
    (net (code "27") (name "Net-(IC5-D)") (class "Default")
      (node (ref "IC5") (pin "3") (pinfunction "D_3") (pintype "bidirectional"))
      (node (ref "J3") (pin "2") (pinfunction "2_2") (pintype "passive"))
    )
    (net (code "28") (name "Net-(IC5-G)") (class "Default")
      (node (ref "IC5") (pin "1") (pinfunction "G_1") (pintype "bidirectional"))
      (node (ref "R24") (pin "1") (pinfunction "1_1") (pintype "passive"))
    )
    (net (code "29") (name "Net-(IC6-D)") (class "Default")
      (node (ref "IC6") (pin "3") (pinfunction "D_3") (pintype "bidirectional"))
      (node (ref "J4") (pin "2") (pinfunction "2_2") (pintype "passive"))
    )
    (net (code "30") (name "Net-(IC6-G)") (class "Default")
      (node (ref "IC6") (pin "1") (pinfunction "G_1") (pintype "bidirectional"))
      (node (ref "R25") (pin "1") (pinfunction "1_1") (pintype "passive"))
    )
    (net (code "31") (name "Net-(IC7-D)") (class "Default")
      (node (ref "IC7") (pin "3") (pinfunction "D_3") (pintype "bidirectional"))
      (node (ref "J5") (pin "2") (pinfunction "2_2") (pintype "passive"))
    )
    (net (code "32") (name "Net-(IC7-G)") (class "Default")
      (node (ref "IC7") (pin "1") (pinfunction "G_1") (pintype "bidirectional"))
      (node (ref "R26") (pin "1") (pinfunction "1_1") (pintype "passive"))
    )
    (net (code "33") (name "Net-(IC8-D)") (class "Default")
      (node (ref "IC8") (pin "3") (pinfunction "D_3") (pintype "bidirectional"))
      (node (ref "LS1") (pin "2") (pinfunction "-_2") (pintype "bidirectional"))
    )
    (net (code "34") (name "Net-(IC8-G)") (class "Default")
      (node (ref "IC8") (pin "1") (pinfunction "G_1") (pintype "bidirectional"))
      (node (ref "R27") (pin "1") (pinfunction "1_1") (pintype "passive"))
    )
    (net (code "35") (name "Net-(IC9-4A)") (class "Default")
      (node (ref "IC9") (pin "9") (pinfunction "4A_9") (pintype "bidirectional"))
      (node (ref "J2") (pin "2") (pinfunction "2_2") (pintype "passive"))
      (node (ref "R30") (pin "1") (pinfunction "1_1") (pintype "passive"))
    )
    (net (code "36") (name "Net-(IC9-5A)") (class "Default")
      (node (ref "IC9") (pin "11") (pinfunction "5A_11") (pintype "bidirectional"))
      (node (ref "J2") (pin "3") (pinfunction "3_3") (pintype "passive"))
      (node (ref "R29") (pin "1") (pinfunction "1_1") (pintype "passive"))
    )
    (net (code "37") (name "Net-(IC9-6A)") (class "Default")
      (node (ref "IC9") (pin "13") (pinfunction "6A_13") (pintype "bidirectional"))
      (node (ref "J2") (pin "4") (pinfunction "4_4") (pintype "passive"))
      (node (ref "R31") (pin "1") (pinfunction "1_1") (pintype "passive"))
    )
    (net (code "38") (name "Net-(LED1-PadC)") (class "Default")
      (node (ref "LED1") (pin "C") (pinfunction "C_C") (pintype "passive"))
      (node (ref "R1") (pin "2") (pinfunction "2_2") (pintype "passive"))
    )
    (net (code "39") (name "Net-(LED2-PadC)") (class "Default")
      (node (ref "LED2") (pin "C") (pinfunction "C_C") (pintype "passive"))
      (node (ref "R4") (pin "2") (pinfunction "2_2") (pintype "passive"))
    )
    (net (code "40") (name "Net-(LED4-PadC)") (class "Default")
      (node (ref "LED4") (pin "C") (pinfunction "C_C") (pintype "passive"))
      (node (ref "R5") (pin "2") (pinfunction "2_2") (pintype "passive"))
    )
    (net (code "41") (name "Net-(LED6-PadC)") (class "Default")
      (node (ref "LED6") (pin "C") (pinfunction "C_C") (pintype "passive"))
      (node (ref "R15") (pin "2") (pinfunction "2_2") (pintype "passive"))
    )
    (net (code "42") (name "Net-(LED7-PadC)") (class "Default")
      (node (ref "LED7") (pin "C") (pinfunction "C_C") (pintype "passive"))
      (node (ref "R16") (pin "2") (pinfunction "2_2") (pintype "passive"))
    )
    (net (code "43") (name "Net-(LED8-PadC)") (class "Default")
      (node (ref "LED8") (pin "C") (pinfunction "C_C") (pintype "passive"))
      (node (ref "R17") (pin "2") (pinfunction "2_2") (pintype "passive"))
    )
    (net (code "44") (name "Net-(LED9-PadC)") (class "Default")
      (node (ref "LED9") (pin "C") (pinfunction "C_C") (pintype "passive"))
      (node (ref "R18") (pin "2") (pinfunction "2_2") (pintype "passive"))
    )
    (net (code "45") (name "Net-(LED10-PadC)") (class "Default")
      (node (ref "LED10") (pin "C") (pinfunction "C_C") (pintype "passive"))
      (node (ref "R19") (pin "2") (pinfunction "2_2") (pintype "passive"))
    )
    (net (code "46") (name "Net-(LED11-PadC)") (class "Default")
      (node (ref "LED11") (pin "C") (pinfunction "C_C") (pintype "passive"))
      (node (ref "R20") (pin "2") (pinfunction "2_2") (pintype "passive"))
    )
    (net (code "47") (name "Net-(LED12-PadC)") (class "Default")
      (node (ref "LED12") (pin "C") (pinfunction "C_C") (pintype "passive"))
      (node (ref "R21") (pin "2") (pinfunction "2_2") (pintype "passive"))
    )
    (net (code "48") (name "Net-(LED13-PadC)") (class "Default")
      (node (ref "LED13") (pin "C") (pinfunction "C_C") (pintype "passive"))
      (node (ref "R22") (pin "2") (pinfunction "2_2") (pintype "passive"))
    )
    (net (code "49") (name "Net-(LED14-PadC)") (class "Default")
      (node (ref "LED14") (pin "C") (pinfunction "C_C") (pintype "passive"))
      (node (ref "R23") (pin "2") (pinfunction "2_2") (pintype "passive"))
    )
    (net (code "50") (name "VCC") (class "Default")
      (node (ref "C16") (pin "1") (pinfunction "1_1") (pintype "passive"))
      (node (ref "C17") (pin "1") (pinfunction "1_1") (pintype "passive"))
      (node (ref "C18") (pin "1") (pinfunction "1_1") (pintype "passive"))
      (node (ref "C19") (pin "1") (pinfunction "1_1") (pintype "passive"))
      (node (ref "C2") (pin "2") (pinfunction "2_2") (pintype "passive"))
      (node (ref "C23") (pin "1") (pinfunction "1_1") (pintype "passive"))
      (node (ref "D1") (pin "1") (pinfunction "K_1") (pintype "bidirectional"))
      (node (ref "J3") (pin "1") (pinfunction "1_1") (pintype "passive"))
      (node (ref "J4") (pin "1") (pinfunction "1_1") (pintype "passive"))
      (node (ref "J5") (pin "1") (pinfunction "1_1") (pintype "passive"))
      (node (ref "LS1") (pin "1") (pinfunction "+_1") (pintype "bidirectional"))
      (node (ref "R2") (pin "1") (pinfunction "1_1") (pintype "passive"))
      (node (ref "TP9") (pin "TP") (pinfunction "TP_TP") (pintype "input"))
    )
    (net (code "51") (name "unconnected-(IC2-1Y-Pad2)") (class "Default")
      (node (ref "IC2") (pin "2") (pinfunction "1Y_2") (pintype "bidirectional"))
    )
    (net (code "52") (name "unconnected-(IC2-2Y-Pad4)") (class "Default")
      (node (ref "IC2") (pin "4") (pinfunction "2Y_4") (pintype "bidirectional"))
    )
    (net (code "53") (name "unconnected-(IC2-3Y-Pad6)") (class "Default")
      (node (ref "IC2") (pin "6") (pinfunction "3Y_6") (pintype "bidirectional"))
    )
    (net (code "54") (name "unconnected-(IC4-3Y-Pad8)") (class "Default")
      (node (ref "IC4") (pin "8") (pinfunction "3Y_8") (pintype "bidirectional"))
    )
    (net (code "55") (name "unconnected-(IC9-1Y-Pad2)") (class "Default")
      (node (ref "IC9") (pin "2") (pinfunction "1Y_2") (pintype "bidirectional"))
    )
    (net (code "56") (name "unconnected-(IC9-2Y-Pad4)") (class "Default")
      (node (ref "IC9") (pin "4") (pinfunction "2Y_4") (pintype "bidirectional"))
    )
    (net (code "57") (name "unconnected-(IC9-3Y-Pad6)") (class "Default")
      (node (ref "IC9") (pin "6") (pinfunction "3Y_6") (pintype "bidirectional"))
    )
  )
)
